# JH-2651M.net
KiCad netlist of a schematic drawn in Altium Designer
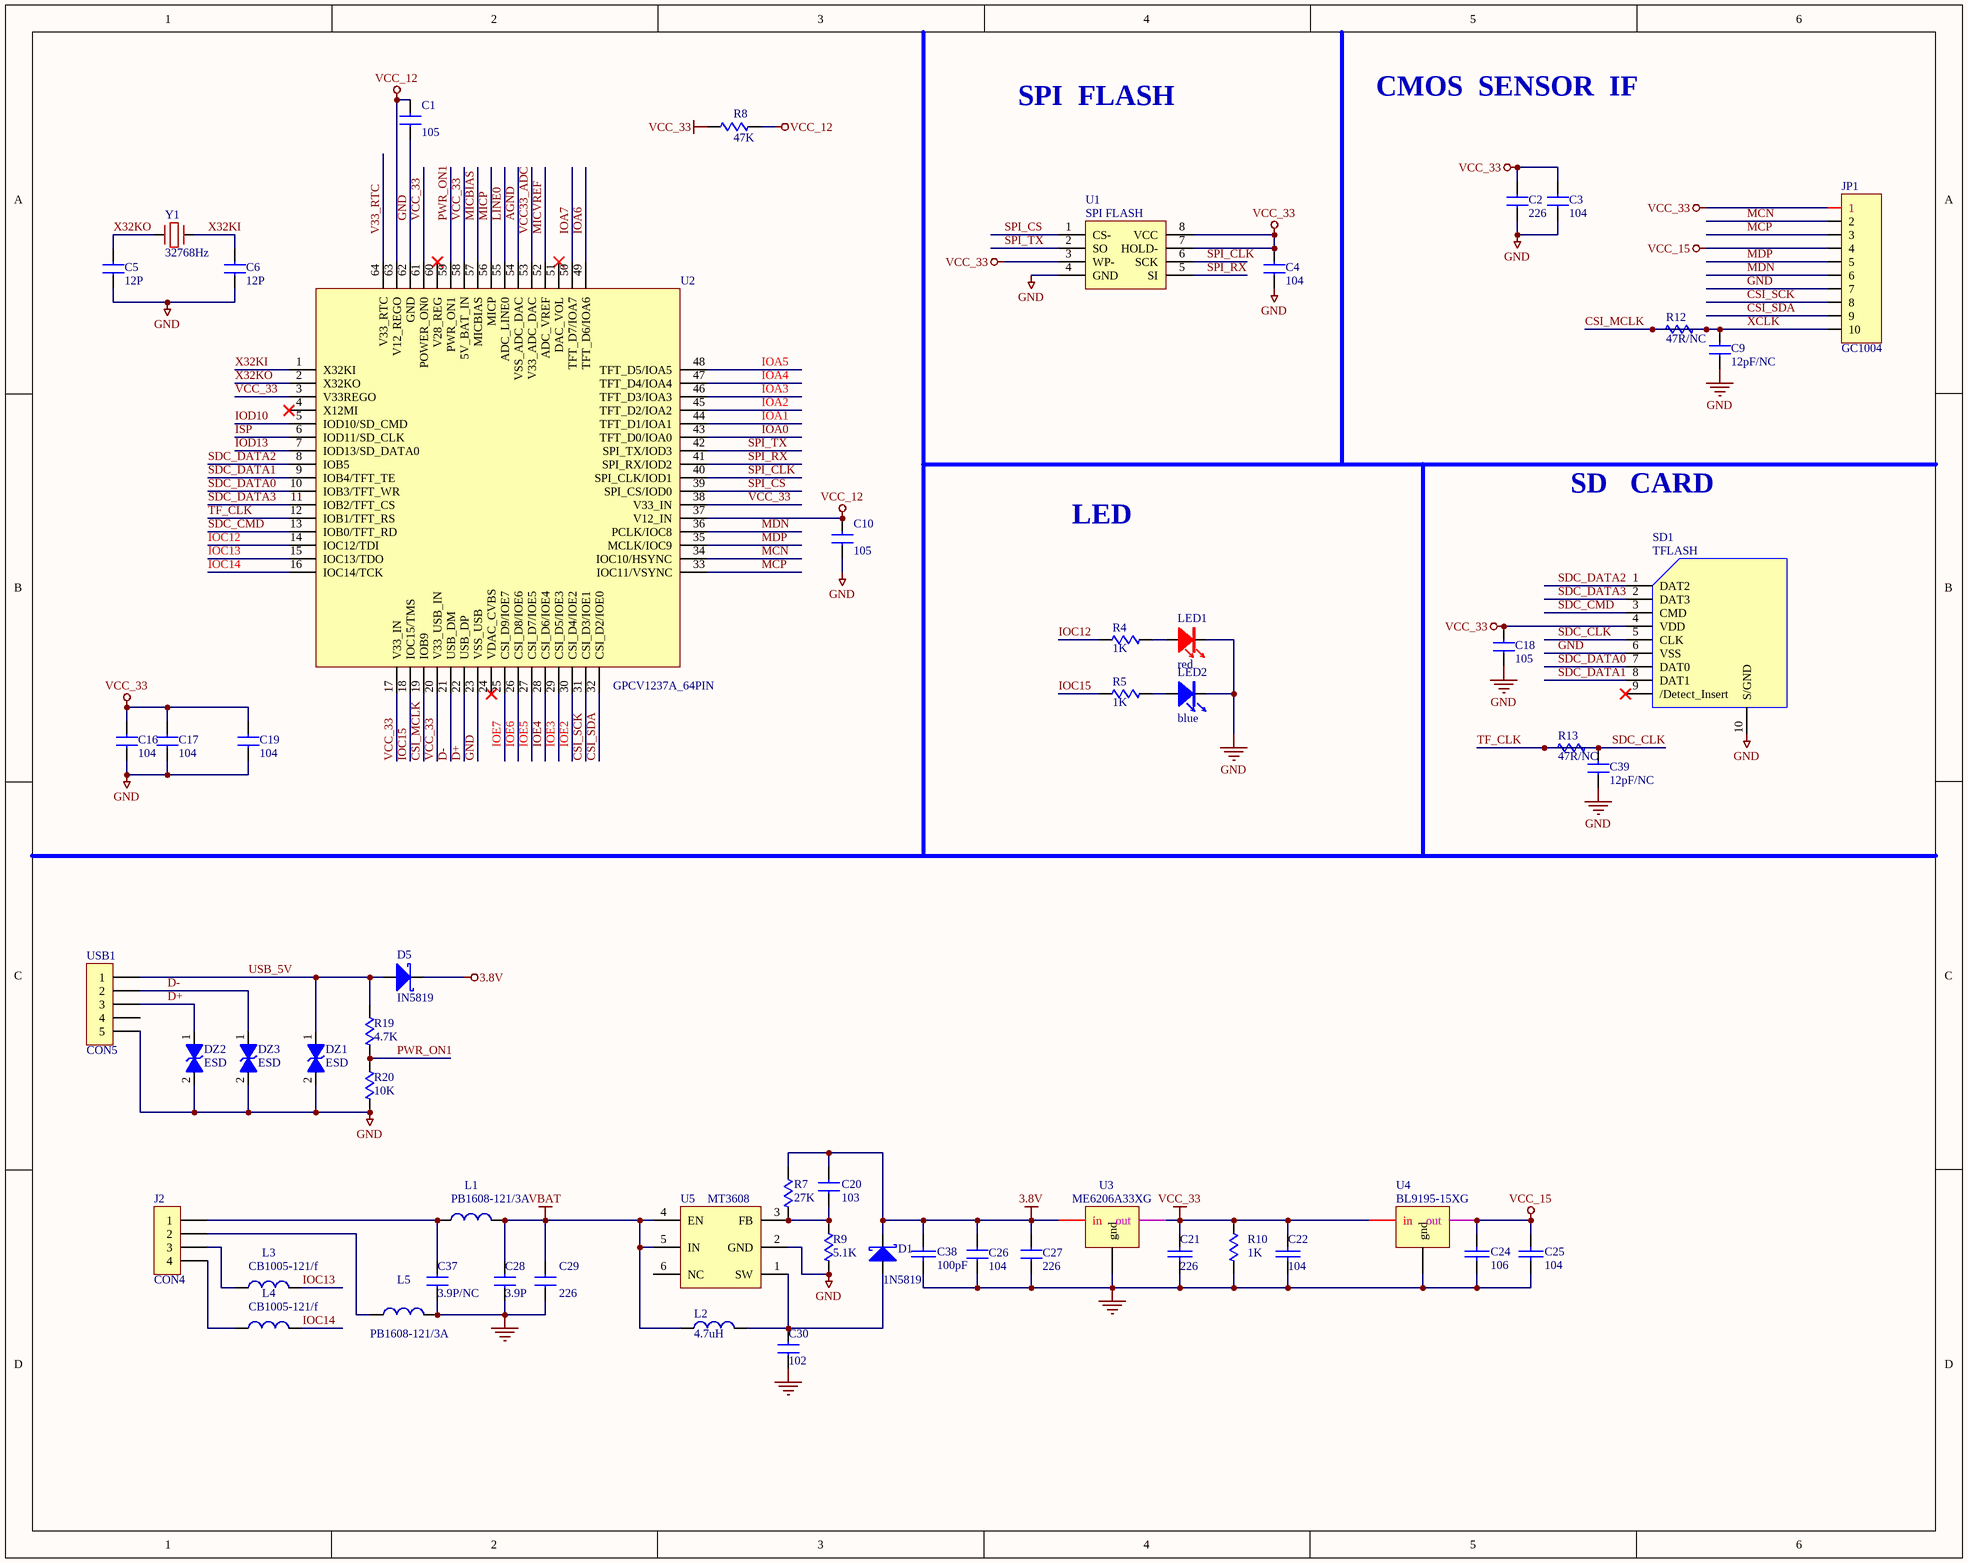
[diagram p0: JH-2651M.SchDoc]

(export (version "E")
  (design (tool "Eeschema 10.0.6"))
  (components
    (comp (ref "C1")
      (value "105")
      (footprint "C0402")
      (description "Capacitor")
      (libsource (lib "*") (part "CAP"))
    )
    (comp (ref "C2")
      (value "226")
      (footprint "C0805")
      (description "Capacitor")
      (libsource (lib "*") (part "CAP"))
    )
    (comp (ref "C3")
      (value "104")
      (footprint "C0402")
      (description "Capacitor")
      (libsource (lib "*") (part "CAP"))
    )
    (comp (ref "C4")
      (value "104")
      (footprint "C0402")
      (description "Capacitor")
      (libsource (lib "*") (part "CAP"))
    )
    (comp (ref "C5")
      (value "12P")
      (footprint "C0402")
      (description "Capacitor")
      (libsource (lib "*") (part "CAP"))
    )
    (comp (ref "C6")
      (value "12P")
      (footprint "C0402")
      (description "Capacitor")
      (libsource (lib "*") (part "CAP"))
    )
    (comp (ref "C9")
      (value "12pF/NC")
      (footprint "C0402")
      (description "Capacitor")
      (libsource (lib "*") (part "CAP"))
    )
    (comp (ref "C10")
      (value "105")
      (footprint "C0402")
      (description "Capacitor")
      (libsource (lib "*") (part "CAP"))
    )
    (comp (ref "C16")
      (value "104")
      (footprint "C0402")
      (description "Capacitor")
      (libsource (lib "*") (part "CAP"))
    )
    (comp (ref "C17")
      (value "104")
      (footprint "C0402")
      (description "Capacitor")
      (libsource (lib "*") (part "CAP"))
    )
    (comp (ref "C18")
      (value "105")
      (footprint "C0402")
      (description "Capacitor")
      (libsource (lib "*") (part "CAP"))
    )
    (comp (ref "C19")
      (value "104")
      (footprint "C0402")
      (description "Capacitor")
      (libsource (lib "*") (part "CAP"))
    )
    (comp (ref "C20")
      (value "103")
      (footprint "C0402")
      (description "Capacitor")
      (libsource (lib "*") (part "CAP"))
    )
    (comp (ref "C21")
      (value "226")
      (footprint "C0805")
      (description "贴片电容")
      (libsource (lib "") (part "CAP_1"))
    )
    (comp (ref "C22")
      (value "104")
      (footprint "C0402")
      (description "贴片电容")
      (libsource (lib "") (part "CAP_1"))
    )
    (comp (ref "C24")
      (value "106")
      (footprint "C0603")
      (description "贴片电容")
      (libsource (lib "") (part "CAP_1"))
    )
    (comp (ref "C25")
      (value "104")
      (footprint "C0402")
      (description "贴片电容")
      (libsource (lib "") (part "CAP_1"))
    )
    (comp (ref "C26")
      (value "104")
      (footprint "C0402")
      (description "Capacitor")
      (libsource (lib "*") (part "CAP"))
    )
    (comp (ref "C27")
      (value "226")
      (footprint "C0805")
      (description "Capacitor")
      (libsource (lib "*") (part "CAP"))
    )
    (comp (ref "C28")
      (value "3.9P")
      (footprint "C0402")
      (description "Capacitor")
      (libsource (lib "*") (part "CAP"))
    )
    (comp (ref "C29")
      (value "226")
      (footprint "C0805")
      (description "Capacitor")
      (libsource (lib "*") (part "CAP"))
    )
    (comp (ref "C30")
      (value "102")
      (footprint "C0402")
      (description "Capacitor")
      (libsource (lib "*") (part "CAP"))
    )
    (comp (ref "C37")
      (value "3.9P/NC")
      (footprint "C0402")
      (description "Capacitor")
      (libsource (lib "*") (part "CAP"))
    )
    (comp (ref "C38")
      (value "100pF")
      (footprint "C0402")
      (description "贴片电容")
      (libsource (lib "") (part "CAP_1"))
    )
    (comp (ref "C39")
      (value "12pF/NC")
      (footprint "C0402")
      (description "Capacitor")
      (libsource (lib "*") (part "CAP"))
    )
    (comp (ref "D1")
      (value "1N5819")
      (footprint "SOD-323")
      (description "Diode(Schottky)")
      (libsource (lib "*") (part "DIODE SCHOTTKY"))
    )
    (comp (ref "D5")
      (value "IN5819")
      (footprint "D0805")
      (description "Diode(Schottky)")
      (libsource (lib "*") (part "DIODE SCHOTTKY"))
    )
    (comp (ref "DZ1") (value "ESD") (footprint "ESD-SOD323") (libsource (lib "*") (part "ESD")))
    (comp (ref "DZ2") (value "ESD") (footprint "ESD-SOD323") (libsource (lib "*") (part "ESD")))
    (comp (ref "DZ3") (value "ESD") (footprint "ESD-SOD323") (libsource (lib "*") (part "ESD")))
    (comp (ref "J2")
      (value "CON4")
      (footprint "SIP4/1.27")
      (description "Connector")
      (libsource (lib "*") (part "CON4"))
    )
    (comp (ref "JP1")
      (value "GC1004")
      (footprint "10pin-mipi/0.7")
      (description "Connector")
      (libsource (lib "*") (part "CON10"))
    )
    (comp (ref "L1")
      (value "PB1608-121/3A")
      (footprint "L0603")
      (description "电感")
      (libsource (lib "*") (part "L-1"))
    )
    (comp (ref "L2")
      (value "4.7uH")
      (footprint "L3015")
      (description "电感")
      (libsource (lib "*") (part "L-1"))
    )
    (comp (ref "L3")
      (value "CB1005-121/f")
      (footprint "L0402")
      (description "电感")
      (libsource (lib "*") (part "L-1"))
    )
    (comp (ref "L4")
      (value "CB1005-121/f")
      (footprint "L0402")
      (description "电感")
      (libsource (lib "*") (part "L-1"))
    )
    (comp (ref "L5")
      (value "PB1608-121/3A")
      (footprint "L0603")
      (description "电感")
      (libsource (lib "*") (part "L-1"))
    )
    (comp (ref "LED1")
      (value "red")
      (footprint "LED0603R")
      (description "LED/红色")
      (libsource (lib "SCH") (part "LED-R"))
    )
    (comp (ref "LED2")
      (value "blue")
      (footprint "LED0603B")
      (description "LED/蓝色")
      (libsource (lib "SCH") (part "LED-B"))
    )
    (comp (ref "R4")
      (value "1K")
      (footprint "R0402")
      (description "Resistor")
      (libsource (lib "*") (part "RES"))
    )
    (comp (ref "R5")
      (value "1K")
      (footprint "R0402")
      (description "Resistor")
      (libsource (lib "*") (part "RES"))
    )
    (comp (ref "R7")
      (value "27K")
      (footprint "R0402")
      (description "Resistor")
      (libsource (lib "*") (part "RES"))
    )
    (comp (ref "R8")
      (value "47K")
      (footprint "R0603")
      (description "Resistor")
      (libsource (lib "*") (part "RES"))
    )
    (comp (ref "R9")
      (value "5.1K")
      (footprint "R0402")
      (description "Resistor")
      (libsource (lib "*") (part "RES"))
    )
    (comp (ref "R10")
      (value "1K")
      (footprint "R0402")
      (description "Resistor")
      (libsource (lib "*") (part "RES"))
    )
    (comp (ref "R12")
      (value "47R/NC")
      (footprint "R0402")
      (description "Resistor")
      (libsource (lib "*") (part "RES"))
    )
    (comp (ref "R13")
      (value "47R/NC")
      (footprint "R0402")
      (description "Resistor")
      (libsource (lib "*") (part "RES"))
    )
    (comp (ref "R19")
      (value "4.7K")
      (footprint "R0402")
      (description "Resistor")
      (libsource (lib "*") (part "RES"))
    )
    (comp (ref "R20")
      (value "10K")
      (footprint "R0402")
      (description "Resistor")
      (libsource (lib "*") (part "RES"))
    )
    (comp (ref "SD1")
      (value "TFLASH")
      (footprint "TFC-0002")
      (description "外卡卡座")
      (libsource (lib "*") (part "SD-MICRO"))
    )
    (comp (ref "U1") (value "SPI FLASH") (footprint "SOP8") (libsource (lib "*") (part "AT25010A")))
    (comp (ref "U2")
      (value "GPCV1237A_64PIN")
      (footprint "LQFP64-0.4")
      (libsource (lib "*") (part "GPCV12417A_64PIN"))
    )
    (comp (ref "U3")
      (value "ME6206A33XG")
      (footprint "SOT23")
      (description "IC(Cmanostat)")
      (libsource (lib "*") (part "IC3"))
    )
    (comp (ref "U4")
      (value "BL9195-15XG")
      (footprint "SOT23")
      (description "IC(Cmanostat)")
      (libsource (lib "*") (part "IC3"))
    )
    (comp (ref "U5") (value "MT3608") (footprint "SOT23-6") (libsource (lib "*") (part "Component_1")))
    (comp (ref "USB1") (value "CON5") (description "Connector") (libsource (lib "*") (part "CON5")))
    (comp (ref "Y1")
      (value "32768Hz")
      (footprint "XTAL-2X6")
      (description "Crystal")
      (libsource (lib "*") (part "CRYSTAL"))
    )
  )
  (nets
    (net (code "1") (name "/AGND") (class "Default")
      (node (ref "U2") (pin "54") (pinfunction "VSS_ADC_DAC_54") (pintype "passive"))
    )
    (net (code "2") (name "/CSI_MCLK") (class "Default")
      (node (ref "C9") (pin "1") (pinfunction "1_1") (pintype "passive"))
      (node (ref "JP1") (pin "10") (pinfunction "10_10") (pintype "passive"))
      (node (ref "R12") (pin "1") (pinfunction "1_1") (pintype "passive"))
      (node (ref "R12") (pin "2") (pinfunction "2_2") (pintype "passive"))
      (node (ref "U2") (pin "19") (pinfunction "IOB9_19") (pintype "passive"))
    )
    (net (code "3") (name "/CSI_SCK") (class "Default")
      (node (ref "JP1") (pin "8") (pinfunction "8_8") (pintype "passive"))
      (node (ref "U2") (pin "31") (pinfunction "CSI_D3/IOE1_31") (pintype "passive"))
    )
    (net (code "4") (name "/CSI_SDA") (class "Default")
      (node (ref "JP1") (pin "9") (pinfunction "9_9") (pintype "passive"))
      (node (ref "U2") (pin "32") (pinfunction "CSI_D2/IOE0_32") (pintype "passive"))
    )
    (net (code "5") (name "/D+") (class "Default")
      (node (ref "DZ2") (pin "1") (pinfunction "1_1") (pintype "passive"))
      (node (ref "U2") (pin "22") (pinfunction "USB_DP_22") (pintype "passive"))
      (node (ref "USB1") (pin "3") (pinfunction "3_3") (pintype "passive"))
    )
    (net (code "6") (name "/D-") (class "Default")
      (node (ref "DZ3") (pin "1") (pinfunction "1_1") (pintype "passive"))
      (node (ref "U2") (pin "21") (pinfunction "USB_DM_21") (pintype "passive"))
      (node (ref "USB1") (pin "2") (pinfunction "2_2") (pintype "passive"))
    )
    (net (code "7") (name "/IOA0") (class "Default")
      (node (ref "U2") (pin "43") (pinfunction "TFT_D0/IOA0_43") (pintype "passive"))
    )
    (net (code "8") (name "/IOA1") (class "Default")
      (node (ref "U2") (pin "44") (pinfunction "TFT_D1/IOA1_44") (pintype "passive"))
    )
    (net (code "9") (name "/IOA2") (class "Default")
      (node (ref "U2") (pin "45") (pinfunction "TFT_D2/IOA2_45") (pintype "passive"))
    )
    (net (code "10") (name "/IOA3") (class "Default")
      (node (ref "U2") (pin "46") (pinfunction "TFT_D3/IOA3_46") (pintype "passive"))
    )
    (net (code "11") (name "/IOA4") (class "Default")
      (node (ref "U2") (pin "47") (pinfunction "TFT_D4/IOA4_47") (pintype "passive"))
    )
    (net (code "12") (name "/IOA5") (class "Default")
      (node (ref "U2") (pin "48") (pinfunction "TFT_D5/IOA5_48") (pintype "passive"))
    )
    (net (code "13") (name "/IOA6") (class "Default")
      (node (ref "U2") (pin "49") (pinfunction "TFT_D6/IOA6_49") (pintype "passive"))
    )
    (net (code "14") (name "/IOA7") (class "Default")
      (node (ref "U2") (pin "50") (pinfunction "TFT_D7/IOA7_50") (pintype "passive"))
    )
    (net (code "15") (name "/IOC12") (class "Default")
      (node (ref "R4") (pin "2") (pinfunction "2_2") (pintype "passive"))
      (node (ref "U2") (pin "14") (pinfunction "IOC12/TDI_14") (pintype "passive"))
    )
    (net (code "16") (name "/IOC13") (class "Default")
      (node (ref "L3") (pin "2") (pinfunction "2_2") (pintype "passive"))
      (node (ref "U2") (pin "15") (pinfunction "IOC13/TDO_15") (pintype "passive"))
    )
    (net (code "17") (name "/IOC14") (class "Default")
      (node (ref "L4") (pin "2") (pinfunction "2_2") (pintype "passive"))
      (node (ref "U2") (pin "16") (pinfunction "IOC14/TCK_16") (pintype "passive"))
    )
    (net (code "18") (name "/IOC15") (class "Default")
      (node (ref "R5") (pin "2") (pinfunction "2_2") (pintype "passive"))
      (node (ref "U2") (pin "18") (pinfunction "IOC15/TMS_18") (pintype "passive"))
    )
    (net (code "19") (name "/IOD10") (class "Default")
      (node (ref "U2") (pin "5") (pinfunction "IOD10/SD_CMD_5") (pintype "passive"))
    )
    (net (code "20") (name "/IOD13") (class "Default")
      (node (ref "U2") (pin "7") (pinfunction "IOD13/SD_DATA0_7") (pintype "passive"))
    )
    (net (code "21") (name "/IOE2") (class "Default")
      (node (ref "U2") (pin "30") (pinfunction "CSI_D4/IOE2_30") (pintype "passive"))
    )
    (net (code "22") (name "/IOE3") (class "Default")
      (node (ref "U2") (pin "29") (pinfunction "CSI_D5/IOE3_29") (pintype "passive"))
    )
    (net (code "23") (name "/IOE4") (class "Default")
      (node (ref "U2") (pin "28") (pinfunction "CSI_D6/IOE4_28") (pintype "passive"))
    )
    (net (code "24") (name "/IOE5") (class "Default")
      (node (ref "U2") (pin "27") (pinfunction "CSI_D7/IOE5_27") (pintype "passive"))
    )
    (net (code "25") (name "/IOE6") (class "Default")
      (node (ref "U2") (pin "26") (pinfunction "CSI_D8/IOE6_26") (pintype "passive"))
    )
    (net (code "26") (name "/IOE7") (class "Default")
      (node (ref "U2") (pin "25") (pinfunction "CSI_D9/IOE7_25") (pintype "passive"))
    )
    (net (code "27") (name "/ISP") (class "Default")
      (node (ref "U2") (pin "6") (pinfunction "IOD11/SD_CLK_6") (pintype "passive"))
    )
    (net (code "28") (name "/LINE0") (class "Default")
      (node (ref "U2") (pin "55") (pinfunction "ADC_LINE0_55") (pintype "passive"))
    )
    (net (code "29") (name "/MCN") (class "Default")
      (node (ref "JP1") (pin "2") (pinfunction "2_2") (pintype "passive"))
      (node (ref "U2") (pin "34") (pinfunction "IOC10/HSYNC_34") (pintype "passive"))
    )
    (net (code "30") (name "/MCP") (class "Default")
      (node (ref "JP1") (pin "3") (pinfunction "3_3") (pintype "passive"))
      (node (ref "U2") (pin "33") (pinfunction "IOC11/VSYNC_33") (pintype "passive"))
    )
    (net (code "31") (name "/MDN") (class "Default")
      (node (ref "JP1") (pin "6") (pinfunction "6_6") (pintype "passive"))
      (node (ref "U2") (pin "36") (pinfunction "PCLK/IOC8_36") (pintype "passive"))
    )
    (net (code "32") (name "/MDP") (class "Default")
      (node (ref "JP1") (pin "5") (pinfunction "5_5") (pintype "passive"))
      (node (ref "U2") (pin "35") (pinfunction "MCLK/IOC9_35") (pintype "passive"))
    )
    (net (code "33") (name "/MICBIAS") (class "Default")
      (node (ref "U2") (pin "57") (pinfunction "MICBIAS_57") (pintype "passive"))
    )
    (net (code "34") (name "/MICP") (class "Default")
      (node (ref "U2") (pin "56") (pinfunction "MICP_56") (pintype "passive"))
    )
    (net (code "35") (name "/MICVREF") (class "Default")
      (node (ref "U2") (pin "52") (pinfunction "ADC_VREF_52") (pintype "passive"))
    )
    (net (code "36") (name "/PWR_ON1") (class "Default")
      (node (ref "R19") (pin "2") (pinfunction "2_2") (pintype "passive"))
      (node (ref "R20") (pin "1") (pinfunction "1_1") (pintype "passive"))
      (node (ref "U2") (pin "59") (pinfunction "PWR_ON1_59") (pintype "passive"))
    )
    (net (code "37") (name "/SDC_CLK") (class "Default")
      (node (ref "C39") (pin "1") (pinfunction "1_1") (pintype "passive"))
      (node (ref "R13") (pin "1") (pinfunction "1_1") (pintype "passive"))
      (node (ref "R13") (pin "2") (pinfunction "2_2") (pintype "passive"))
      (node (ref "SD1") (pin "5") (pinfunction "CLK_5") (pintype "power_in"))
      (node (ref "U2") (pin "12") (pinfunction "IOB1/TFT_RS_12") (pintype "passive"))
    )
    (net (code "38") (name "/SDC_CMD") (class "Default")
      (node (ref "SD1") (pin "3") (pinfunction "CMD_3") (pintype "power_in"))
      (node (ref "U2") (pin "13") (pinfunction "IOB0/TFT_RD_13") (pintype "passive"))
    )
    (net (code "39") (name "/SDC_DATA0") (class "Default")
      (node (ref "SD1") (pin "7") (pinfunction "DAT0_7") (pintype "power_in"))
      (node (ref "U2") (pin "10") (pinfunction "IOB3/TFT_WR_10") (pintype "passive"))
    )
    (net (code "40") (name "/SDC_DATA1") (class "Default")
      (node (ref "SD1") (pin "8") (pinfunction "DAT1_8") (pintype "power_in"))
      (node (ref "U2") (pin "9") (pinfunction "IOB4/TFT_TE_9") (pintype "passive"))
    )
    (net (code "41") (name "/SDC_DATA2") (class "Default")
      (node (ref "SD1") (pin "1") (pinfunction "DAT2_1") (pintype "power_in"))
      (node (ref "U2") (pin "8") (pinfunction "IOB5_8") (pintype "passive"))
    )
    (net (code "42") (name "/SDC_DATA3") (class "Default")
      (node (ref "SD1") (pin "2") (pinfunction "DAT3_2") (pintype "power_in"))
      (node (ref "U2") (pin "11") (pinfunction "IOB2/TFT_CS_11") (pintype "passive"))
    )
    (net (code "43") (name "/SPI_CLK") (class "Default")
      (node (ref "U1") (pin "6") (pinfunction "SCK_6") (pintype "passive"))
      (node (ref "U2") (pin "40") (pinfunction "SPI_CLK/IOD1_40") (pintype "passive"))
    )
    (net (code "44") (name "/SPI_CS") (class "Default")
      (node (ref "U1") (pin "1") (pinfunction "CS-_1") (pintype "passive"))
      (node (ref "U2") (pin "39") (pinfunction "SPI_CS/IOD0_39") (pintype "passive"))
    )
    (net (code "45") (name "/SPI_RX") (class "Default")
      (node (ref "U1") (pin "5") (pinfunction "SI_5") (pintype "passive"))
      (node (ref "U2") (pin "41") (pinfunction "SPI_RX/IOD2_41") (pintype "passive"))
    )
    (net (code "46") (name "/SPI_TX") (class "Default")
      (node (ref "U1") (pin "2") (pinfunction "SO_2") (pintype "passive"))
      (node (ref "U2") (pin "42") (pinfunction "SPI_TX/IOD3_42") (pintype "passive"))
    )
    (net (code "47") (name "/USB_5V") (class "Default")
      (node (ref "D5") (pin "1") (pinfunction "A_1") (pintype "passive"))
      (node (ref "DZ1") (pin "1") (pinfunction "1_1") (pintype "passive"))
      (node (ref "R19") (pin "1") (pinfunction "1_1") (pintype "passive"))
      (node (ref "USB1") (pin "1") (pinfunction "1_1") (pintype "passive"))
    )
    (net (code "48") (name "/V33_RTC") (class "Default")
      (node (ref "U2") (pin "64") (pinfunction "V33_RTC_64") (pintype "passive"))
    )
    (net (code "49") (name "/VCC33_ADC") (class "Default")
      (node (ref "U2") (pin "53") (pinfunction "V33_ADC_DAC_53") (pintype "passive"))
    )
    (net (code "50") (name "/X32KI") (class "Default")
      (node (ref "C6") (pin "1") (pinfunction "1_1") (pintype "passive"))
      (node (ref "U2") (pin "1") (pinfunction "X32KI_1") (pintype "passive"))
      (node (ref "Y1") (pin "2") (pinfunction "2_2") (pintype "passive"))
    )
    (net (code "51") (name "/X32KO") (class "Default")
      (node (ref "C5") (pin "1") (pinfunction "1_1") (pintype "passive"))
      (node (ref "U2") (pin "2") (pinfunction "X32KO_2") (pintype "passive"))
      (node (ref "Y1") (pin "1") (pinfunction "1_1") (pintype "passive"))
    )
    (net (code "52") (name "3.8V") (class "Default")
      (node (ref "C20") (pin "1") (pinfunction "1_1") (pintype "passive"))
      (node (ref "C26") (pin "1") (pinfunction "1_1") (pintype "passive"))
      (node (ref "C27") (pin "1") (pinfunction "1_1") (pintype "passive"))
      (node (ref "C38") (pin "1") (pinfunction "1_1") (pintype "passive"))
      (node (ref "D1") (pin "2") (pinfunction "K_2") (pintype "passive"))
      (node (ref "D5") (pin "2") (pinfunction "K_2") (pintype "passive"))
      (node (ref "R7") (pin "1") (pinfunction "1_1") (pintype "passive"))
      (node (ref "U3") (pin "3") (pinfunction "in_3") (pintype "passive"))
    )
    (net (code "53") (name "GND") (class "Default")
      (node (ref "C1") (pin "2") (pinfunction "2_2") (pintype "passive"))
      (node (ref "C10") (pin "2") (pinfunction "2_2") (pintype "passive"))
      (node (ref "C16") (pin "2") (pinfunction "2_2") (pintype "passive"))
      (node (ref "C17") (pin "2") (pinfunction "2_2") (pintype "passive"))
      (node (ref "C18") (pin "2") (pinfunction "2_2") (pintype "passive"))
      (node (ref "C19") (pin "2") (pinfunction "2_2") (pintype "passive"))
      (node (ref "C2") (pin "2") (pinfunction "2_2") (pintype "passive"))
      (node (ref "C21") (pin "2") (pinfunction "2_2") (pintype "passive"))
      (node (ref "C22") (pin "2") (pinfunction "2_2") (pintype "passive"))
      (node (ref "C24") (pin "2") (pinfunction "2_2") (pintype "passive"))
      (node (ref "C25") (pin "2") (pinfunction "2_2") (pintype "passive"))
      (node (ref "C26") (pin "2") (pinfunction "2_2") (pintype "passive"))
      (node (ref "C27") (pin "2") (pinfunction "2_2") (pintype "passive"))
      (node (ref "C28") (pin "2") (pinfunction "2_2") (pintype "passive"))
      (node (ref "C29") (pin "2") (pinfunction "2_2") (pintype "passive"))
      (node (ref "C3") (pin "2") (pinfunction "2_2") (pintype "passive"))
      (node (ref "C30") (pin "1") (pinfunction "1_1") (pintype "passive"))
      (node (ref "C37") (pin "2") (pinfunction "2_2") (pintype "passive"))
      (node (ref "C38") (pin "2") (pinfunction "2_2") (pintype "passive"))
      (node (ref "C39") (pin "2") (pinfunction "2_2") (pintype "passive"))
      (node (ref "C4") (pin "2") (pinfunction "2_2") (pintype "passive"))
      (node (ref "C5") (pin "2") (pinfunction "2_2") (pintype "passive"))
      (node (ref "C6") (pin "2") (pinfunction "2_2") (pintype "passive"))
      (node (ref "C9") (pin "2") (pinfunction "2_2") (pintype "passive"))
      (node (ref "DZ1") (pin "2") (pinfunction "2_2") (pintype "passive"))
      (node (ref "DZ2") (pin "2") (pinfunction "2_2") (pintype "passive"))
      (node (ref "DZ3") (pin "2") (pinfunction "2_2") (pintype "passive"))
      (node (ref "JP1") (pin "7") (pinfunction "7_7") (pintype "passive"))
      (node (ref "L5") (pin "2") (pinfunction "2_2") (pintype "passive"))
      (node (ref "LED1") (pin "2") (pinfunction "K_2") (pintype "passive"))
      (node (ref "LED2") (pin "2") (pinfunction "K_2") (pintype "passive"))
      (node (ref "R10") (pin "2") (pinfunction "2_2") (pintype "passive"))
      (node (ref "R20") (pin "2") (pinfunction "2_2") (pintype "passive"))
      (node (ref "R9") (pin "2") (pinfunction "2_2") (pintype "passive"))
      (node (ref "SD1") (pin "10") (pinfunction "S/GND_10") (pintype "power_in"))
      (node (ref "SD1") (pin "6") (pinfunction "VSS_6") (pintype "power_in"))
      (node (ref "U1") (pin "4") (pinfunction "GND_4") (pintype "passive"))
      (node (ref "U2") (pin "23") (pinfunction "VSS_USB_23") (pintype "passive"))
      (node (ref "U2") (pin "62") (pinfunction "GND_62") (pintype "passive"))
      (node (ref "U3") (pin "1") (pinfunction "gnd_1") (pintype "passive"))
      (node (ref "U4") (pin "1") (pinfunction "gnd_1") (pintype "passive"))
      (node (ref "U5") (pin "2") (pinfunction "GND_2") (pintype "passive"))
      (node (ref "USB1") (pin "5") (pinfunction "5_5") (pintype "passive"))
    )
    (net (code "54") (name "Net-(C37-Pad1)") (class "Default")
      (node (ref "C37") (pin "1") (pinfunction "1_1") (pintype "passive"))
      (node (ref "J2") (pin "1") (pinfunction "1_1") (pintype "passive"))
      (node (ref "L1") (pin "1") (pinfunction "1_1") (pintype "passive"))
    )
    (net (code "55") (name "Net-(D1-A)") (class "Default")
      (node (ref "C30") (pin "2") (pinfunction "2_2") (pintype "passive"))
      (node (ref "D1") (pin "1") (pinfunction "A_1") (pintype "passive"))
      (node (ref "L2") (pin "2") (pinfunction "2_2") (pintype "passive"))
      (node (ref "U5") (pin "1") (pinfunction "SW_1") (pintype "passive"))
    )
    (net (code "56") (name "Net-(J2-Pad2)") (class "Default")
      (node (ref "J2") (pin "2") (pinfunction "2_2") (pintype "passive"))
      (node (ref "L5") (pin "1") (pinfunction "1_1") (pintype "passive"))
    )
    (net (code "57") (name "Net-(J2-Pad3)") (class "Default")
      (node (ref "J2") (pin "3") (pinfunction "3_3") (pintype "passive"))
      (node (ref "L3") (pin "1") (pinfunction "1_1") (pintype "passive"))
    )
    (net (code "58") (name "Net-(J2-Pad4)") (class "Default")
      (node (ref "J2") (pin "4") (pinfunction "4_4") (pintype "passive"))
      (node (ref "L4") (pin "1") (pinfunction "1_1") (pintype "passive"))
    )
    (net (code "59") (name "Net-(LED1-A)") (class "Default")
      (node (ref "LED1") (pin "1") (pinfunction "A_1") (pintype "passive"))
      (node (ref "R4") (pin "1") (pinfunction "1_1") (pintype "passive"))
    )
    (net (code "60") (name "Net-(LED2-A)") (class "Default")
      (node (ref "LED2") (pin "1") (pinfunction "A_1") (pintype "passive"))
      (node (ref "R5") (pin "1") (pinfunction "1_1") (pintype "passive"))
    )
    (net (code "61") (name "Net-(U5-FB)") (class "Default")
      (node (ref "C20") (pin "2") (pinfunction "2_2") (pintype "passive"))
      (node (ref "R7") (pin "2") (pinfunction "2_2") (pintype "passive"))
      (node (ref "R9") (pin "1") (pinfunction "1_1") (pintype "passive"))
      (node (ref "U5") (pin "3") (pinfunction "FB_3") (pintype "passive"))
    )
    (net (code "62") (name "VBAT") (class "Default")
      (node (ref "C28") (pin "1") (pinfunction "1_1") (pintype "passive"))
      (node (ref "C29") (pin "1") (pinfunction "1_1") (pintype "passive"))
      (node (ref "L1") (pin "2") (pinfunction "2_2") (pintype "passive"))
      (node (ref "L2") (pin "1") (pinfunction "1_1") (pintype "passive"))
      (node (ref "U5") (pin "4") (pinfunction "EN_4") (pintype "passive"))
      (node (ref "U5") (pin "5") (pinfunction "IN_5") (pintype "passive"))
    )
    (net (code "63") (name "VCC_12") (class "Default")
      (node (ref "C1") (pin "1") (pinfunction "1_1") (pintype "passive"))
      (node (ref "C10") (pin "1") (pinfunction "1_1") (pintype "passive"))
      (node (ref "R8") (pin "2") (pinfunction "2_2") (pintype "passive"))
      (node (ref "U2") (pin "37") (pinfunction "V12_IN_37") (pintype "passive"))
      (node (ref "U2") (pin "63") (pinfunction "V12_REGO_63") (pintype "passive"))
    )
    (net (code "64") (name "VCC_15") (class "Default")
      (node (ref "C24") (pin "1") (pinfunction "1_1") (pintype "passive"))
      (node (ref "C25") (pin "1") (pinfunction "1_1") (pintype "passive"))
      (node (ref "JP1") (pin "4") (pinfunction "4_4") (pintype "passive"))
      (node (ref "U4") (pin "2") (pinfunction "out_2") (pintype "passive"))
    )
    (net (code "65") (name "VCC_33") (class "Default")
      (node (ref "C16") (pin "1") (pinfunction "1_1") (pintype "passive"))
      (node (ref "C17") (pin "1") (pinfunction "1_1") (pintype "passive"))
      (node (ref "C18") (pin "1") (pinfunction "1_1") (pintype "passive"))
      (node (ref "C19") (pin "1") (pinfunction "1_1") (pintype "passive"))
      (node (ref "C2") (pin "1") (pinfunction "1_1") (pintype "passive"))
      (node (ref "C21") (pin "1") (pinfunction "1_1") (pintype "passive"))
      (node (ref "C22") (pin "1") (pinfunction "1_1") (pintype "passive"))
      (node (ref "C3") (pin "1") (pinfunction "1_1") (pintype "passive"))
      (node (ref "C4") (pin "1") (pinfunction "1_1") (pintype "passive"))
      (node (ref "JP1") (pin "1") (pinfunction "1_1") (pintype "passive"))
      (node (ref "R10") (pin "1") (pinfunction "1_1") (pintype "passive"))
      (node (ref "R8") (pin "1") (pinfunction "1_1") (pintype "passive"))
      (node (ref "SD1") (pin "4") (pinfunction "VDD_4") (pintype "power_in"))
      (node (ref "U1") (pin "3") (pinfunction "WP-_3") (pintype "passive"))
      (node (ref "U1") (pin "7") (pinfunction "HOLD-_7") (pintype "passive"))
      (node (ref "U1") (pin "8") (pinfunction "VCC_8") (pintype "passive"))
      (node (ref "U2") (pin "17") (pinfunction "V33_IN_17") (pintype "passive"))
      (node (ref "U2") (pin "20") (pinfunction "V33_USB_IN_20") (pintype "passive"))
      (node (ref "U2") (pin "3") (pinfunction "V33REGO_3") (pintype "passive"))
      (node (ref "U2") (pin "38") (pinfunction "V33_IN_38") (pintype "passive"))
      (node (ref "U2") (pin "58") (pinfunction "5V_BAT_IN_58") (pintype "passive"))
      (node (ref "U2") (pin "61") (pinfunction "POWER_ON0_61") (pintype "passive"))
      (node (ref "U3") (pin "2") (pinfunction "out_2") (pintype "passive"))
      (node (ref "U4") (pin "3") (pinfunction "in_3") (pintype "passive"))
    )
    (net (code "66") (name "unconnected-(SD1-{slash}Detect_Insert-Pad9)") (class "Default")
      (node (ref "SD1") (pin "9") (pinfunction "/Detect_Insert_9") (pintype "power_in+no_connect"))
    )
    (net (code "67") (name "unconnected-(U2-DAC_VOL-Pad51)") (class "Default")
      (node (ref "U2") (pin "51") (pinfunction "DAC_VOL_51") (pintype "passive+no_connect"))
    )
    (net (code "68") (name "unconnected-(U2-V28_REG-Pad60)") (class "Default")
      (node (ref "U2") (pin "60") (pinfunction "V28_REG_60") (pintype "passive+no_connect"))
    )
    (net (code "69") (name "unconnected-(U2-VDAC_CVBS-Pad24)") (class "Default")
      (node (ref "U2") (pin "24") (pinfunction "VDAC_CVBS_24") (pintype "passive+no_connect"))
    )
    (net (code "70") (name "unconnected-(U2-X12MI-Pad4)") (class "Default")
      (node (ref "U2") (pin "4") (pinfunction "X12MI_4") (pintype "passive+no_connect"))
    )
    (net (code "71") (name "unconnected-(U5-NC-Pad6)") (class "Default")
      (node (ref "U5") (pin "6") (pinfunction "NC_6") (pintype "passive"))
    )
    (net (code "72") (name "unconnected-(USB1-Pad4)") (class "Default")
      (node (ref "USB1") (pin "4") (pinfunction "4_4") (pintype "passive"))
    )
  )
)
